# shredmaster.net
KiCad netlist of a schematic drawn in EAGLE
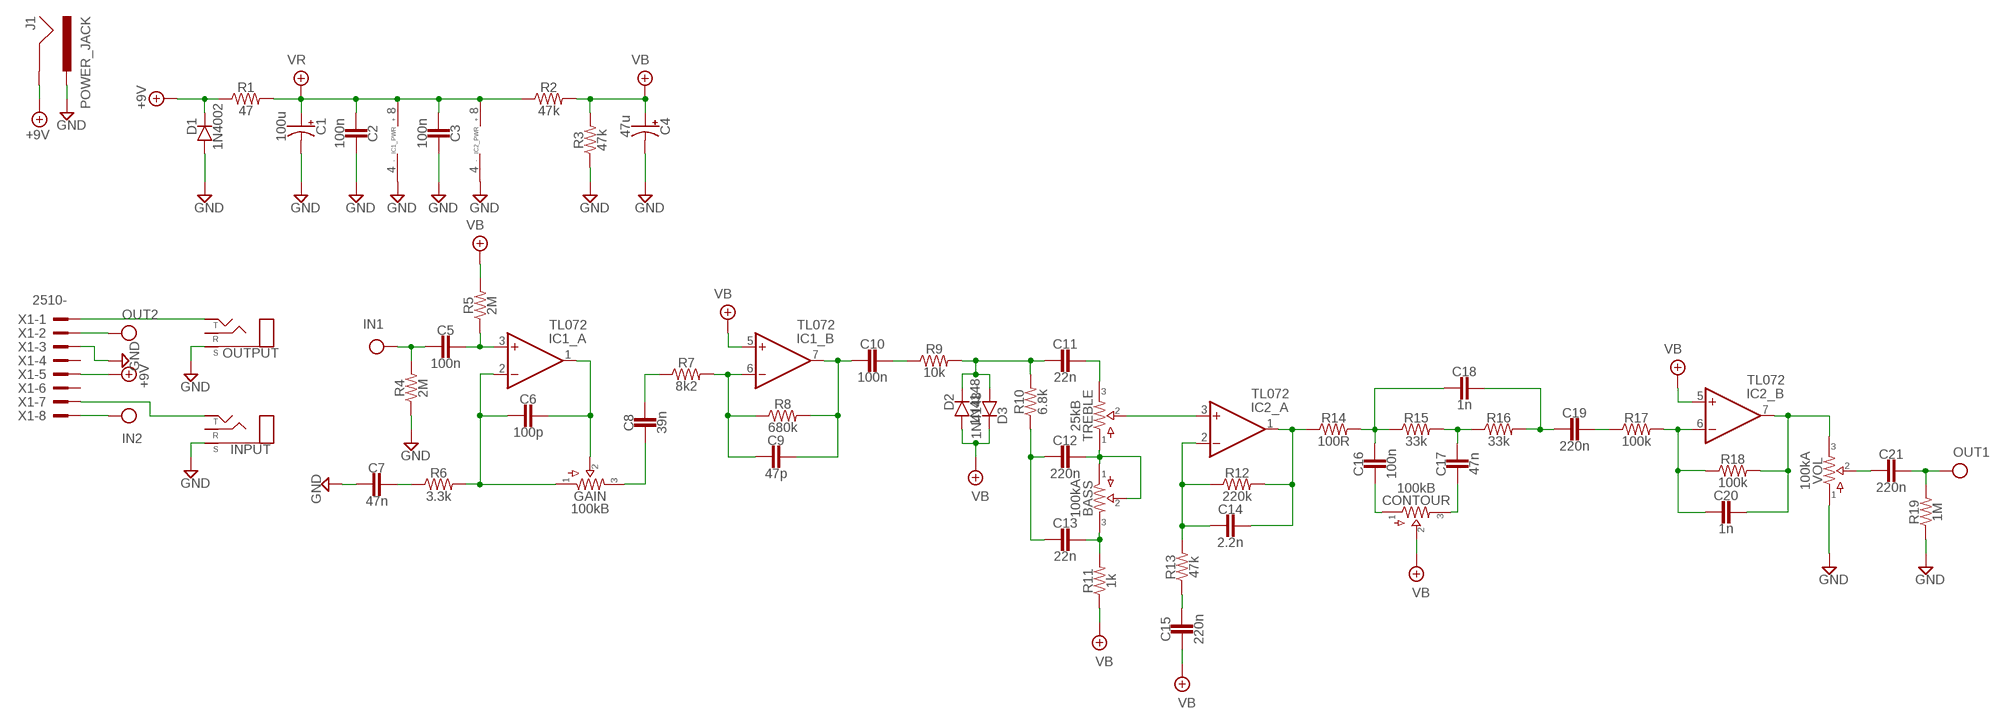
[diagram p0: schematic, sheet 1]

(export (version "E")
  (design (tool "Eeschema 10.0.6"))
  (components
    (comp (ref "BASS")
      (value "100kA")
      (footprint "eagle-import:16MM")
      (libsource (lib "eagle-import") (part "POTS16MM"))
    )
    (comp (ref "C1")
      (value "100u")
      (footprint "eagle-import:040_020")
      (libsource (lib "eagle-import") (part "0400"))
    )
    (comp (ref "C2")
      (value "100n")
      (footprint "eagle-import:050X030_025_2")
      (libsource (lib "eagle-import") (part "CER/FILM2"))
    )
    (comp (ref "C3")
      (value "100n")
      (footprint "eagle-import:050X030_025_2")
      (libsource (lib "eagle-import") (part "CER/FILM2"))
    )
    (comp (ref "C4")
      (value "47u")
      (footprint "eagle-import:040_020")
      (libsource (lib "eagle-import") (part "0400"))
    )
    (comp (ref "C5")
      (value "100n")
      (footprint "eagle-import:BOX_SMALL")
      (libsource (lib "eagle-import") (part "CER/FILMBOX.1"))
    )
    (comp (ref "C6")
      (value "100p")
      (footprint "eagle-import:050X030_025_2")
      (libsource (lib "eagle-import") (part "CER/FILM2"))
    )
    (comp (ref "C7")
      (value "47n")
      (footprint "eagle-import:BOX_SMALL")
      (libsource (lib "eagle-import") (part "CER/FILMBOX.1"))
    )
    (comp (ref "C8")
      (value "39n")
      (footprint "eagle-import:BOX_SMALL")
      (libsource (lib "eagle-import") (part "CER/FILMBOX.1"))
    )
    (comp (ref "C9")
      (value "47p")
      (footprint "eagle-import:050X030_025_2")
      (libsource (lib "eagle-import") (part "CER/FILM2"))
    )
    (comp (ref "C10")
      (value "100n")
      (footprint "eagle-import:BOX_SMALL")
      (libsource (lib "eagle-import") (part "CER/FILMBOX.1"))
    )
    (comp (ref "C11")
      (value "22n")
      (footprint "eagle-import:BOX_SMALL")
      (libsource (lib "eagle-import") (part "CER/FILMBOX.1"))
    )
    (comp (ref "C12")
      (value "220n")
      (footprint "eagle-import:BOX_SMALL")
      (libsource (lib "eagle-import") (part "CER/FILMBOX.1"))
    )
    (comp (ref "C13")
      (value "22n")
      (footprint "eagle-import:BOX_SMALL")
      (libsource (lib "eagle-import") (part "CER/FILMBOX.1"))
    )
    (comp (ref "C14")
      (value "2.2n")
      (footprint "eagle-import:BOX_SMALL")
      (libsource (lib "eagle-import") (part "CER/FILMBOX.1"))
    )
    (comp (ref "C15")
      (value "220n")
      (footprint "eagle-import:BOX_SMALL")
      (libsource (lib "eagle-import") (part "CER/FILMBOX.1"))
    )
    (comp (ref "C16")
      (value "100n")
      (footprint "eagle-import:BOX_SMALL")
      (libsource (lib "eagle-import") (part "CER/FILMBOX.1"))
    )
    (comp (ref "C17")
      (value "47n")
      (footprint "eagle-import:BOX_SMALL")
      (libsource (lib "eagle-import") (part "CER/FILMBOX.1"))
    )
    (comp (ref "C18")
      (value "1n")
      (footprint "eagle-import:BOX_SMALL")
      (libsource (lib "eagle-import") (part "CER/FILMBOX.1"))
    )
    (comp (ref "C19")
      (value "220n")
      (footprint "eagle-import:BOX_SMALL")
      (libsource (lib "eagle-import") (part "CER/FILMBOX.1"))
    )
    (comp (ref "C20")
      (value "1n")
      (footprint "eagle-import:BOX_SMALL")
      (libsource (lib "eagle-import") (part "CER/FILMBOX.1"))
    )
    (comp (ref "C21")
      (value "220n")
      (footprint "eagle-import:BOX_SMALL")
      (libsource (lib "eagle-import") (part "CER/FILMBOX.1"))
    )
    (comp (ref "CONTOUR")
      (value "100kB")
      (footprint "eagle-import:16MM")
      (libsource (lib "eagle-import") (part "POTS16MM"))
    )
    (comp (ref "D1")
      (value "1N4002")
      (footprint "eagle-import:DO41-2")
      (libsource (lib "eagle-import") (part "DO41.2"))
    )
    (comp (ref "D2")
      (value "1N4148")
      (footprint "eagle-import:DO35-2")
      (libsource (lib "eagle-import") (part "DO35.2"))
    )
    (comp (ref "D3")
      (value "1N4148")
      (footprint "eagle-import:DO35-2")
      (libsource (lib "eagle-import") (part "DO35.2"))
    )
    (comp (ref "GAIN")
      (value "100kB")
      (footprint "eagle-import:16MM")
      (libsource (lib "eagle-import") (part "POTS16MM"))
    )
    (comp (ref "IC1")
      (value "TL072")
      (footprint "eagle-import:DIL08")
      (libsource (lib "eagle-import") (part "DUALTH"))
    )
    (comp (ref "IC2")
      (value "TL072")
      (footprint "eagle-import:DIL08")
      (libsource (lib "eagle-import") (part "DUALTH"))
    )
    (comp (ref "INPUT")
      (value "STEREONMJ")
      (footprint "eagle-import:NMJ6HCD2")
      (libsource (lib "eagle-import") (part "STEREONMJ"))
    )
    (comp (ref "J1")
      (value "POWER_JACK")
      (footprint "eagle-import:POWER_JACK_PTH")
      (libsource (lib "eagle-import") (part "POWER_JACK"))
    )
    (comp (ref "OUTPUT")
      (value "STEREONMJ")
      (footprint "eagle-import:NMJ6HCD2")
      (libsource (lib "eagle-import") (part "STEREONMJ"))
    )
    (comp (ref "R1")
      (value "47")
      (footprint "eagle-import:R0207_3")
      (libsource (lib "eagle-import") (part "R_.3B"))
    )
    (comp (ref "R2")
      (value "47k")
      (footprint "eagle-import:R0207_3")
      (libsource (lib "eagle-import") (part "R_.3B"))
    )
    (comp (ref "R3")
      (value "47k")
      (footprint "eagle-import:R0207_3")
      (libsource (lib "eagle-import") (part "R_.3B"))
    )
    (comp (ref "R4")
      (value "2M")
      (footprint "eagle-import:R0207_3")
      (libsource (lib "eagle-import") (part "R_.3B"))
    )
    (comp (ref "R5")
      (value "2M")
      (footprint "eagle-import:R0207_3")
      (libsource (lib "eagle-import") (part "R_.3B"))
    )
    (comp (ref "R6")
      (value "3.3k")
      (footprint "eagle-import:R0207_3")
      (libsource (lib "eagle-import") (part "R_.3B"))
    )
    (comp (ref "R7")
      (value "8k2")
      (footprint "eagle-import:R0207_3")
      (libsource (lib "eagle-import") (part "R_.3B"))
    )
    (comp (ref "R8")
      (value "680k")
      (footprint "eagle-import:R0207_3")
      (libsource (lib "eagle-import") (part "R_.3B"))
    )
    (comp (ref "R9")
      (value "10k")
      (footprint "eagle-import:R0207_3")
      (libsource (lib "eagle-import") (part "R_.3B"))
    )
    (comp (ref "R10")
      (value "6.8k")
      (footprint "eagle-import:R0207_3")
      (libsource (lib "eagle-import") (part "R_.3B"))
    )
    (comp (ref "R11")
      (value "1k")
      (footprint "eagle-import:R0207_3")
      (libsource (lib "eagle-import") (part "R_.3B"))
    )
    (comp (ref "R12")
      (value "220k")
      (footprint "eagle-import:R0207_3")
      (libsource (lib "eagle-import") (part "R_.3B"))
    )
    (comp (ref "R13")
      (value "47k")
      (footprint "eagle-import:R0207_3")
      (libsource (lib "eagle-import") (part "R_.3B"))
    )
    (comp (ref "R14")
      (value "100R")
      (footprint "eagle-import:R0207_3")
      (libsource (lib "eagle-import") (part "R_.3B"))
    )
    (comp (ref "R15")
      (value "33k")
      (footprint "eagle-import:R0207_3")
      (libsource (lib "eagle-import") (part "R_.3B"))
    )
    (comp (ref "R16")
      (value "33k")
      (footprint "eagle-import:R0207_3")
      (libsource (lib "eagle-import") (part "R_.3B"))
    )
    (comp (ref "R17")
      (value "100k")
      (footprint "eagle-import:R0207_3")
      (libsource (lib "eagle-import") (part "R_.3B"))
    )
    (comp (ref "R18")
      (value "100k")
      (footprint "eagle-import:R0207_3")
      (libsource (lib "eagle-import") (part "R_.3B"))
    )
    (comp (ref "R19")
      (value "1M")
      (footprint "eagle-import:R0207_3")
      (libsource (lib "eagle-import") (part "R_.3B"))
    )
    (comp (ref "TREBLE")
      (value "25kB")
      (footprint "eagle-import:16MM")
      (libsource (lib "eagle-import") (part "POTS16MM"))
    )
    (comp (ref "VOL")
      (value "100kA")
      (footprint "eagle-import:16MM")
      (libsource (lib "eagle-import") (part "POTS16MM"))
    )
    (comp (ref "X1")
      (value "2510-")
      (footprint "eagle-import:PAK100_2500-10")
      (fields (field (name "MF") "3M") (field (name "MPN") "2510-6002UB"))
      (libsource (lib "eagle-import") (part "2510-"))
    )
  )
  (nets
    (net (code "1") (name "+9V") (class "Default")
      (node (ref "D1") (pin "C") (pinfunction "C_C") (pintype "passive"))
      (node (ref "J1") (pin "GND") (pinfunction "GND_GND") (pintype "bidirectional"))
      (node (ref "R1") (pin "1") (pinfunction "1_1") (pintype "passive"))
      (node (ref "X1") (pin "5") (pinfunction "KL_5") (pintype "passive"))
    )
    (net (code "2") (name "GND") (class "Default")
      (node (ref "C1") (pin "-") (pinfunction "-_-") (pintype "passive"))
      (node (ref "C2") (pin "1") (pinfunction "1_1") (pintype "passive"))
      (node (ref "C3") (pin "1") (pinfunction "1_1") (pintype "passive"))
      (node (ref "C4") (pin "-") (pinfunction "-_-") (pintype "passive"))
      (node (ref "C7") (pin "2") (pinfunction "2_2") (pintype "passive"))
      (node (ref "D1") (pin "A") (pinfunction "A_A") (pintype "passive"))
      (node (ref "IC1") (pin "4") (pinfunction "V-_4") (pintype "power_in"))
      (node (ref "IC2") (pin "4") (pinfunction "V-_4") (pintype "power_in"))
      (node (ref "INPUT") (pin "S") (pinfunction "S_S") (pintype "passive"))
      (node (ref "J1") (pin "PWR") (pinfunction "PWR_PWR") (pintype "bidirectional"))
      (node (ref "OUTPUT") (pin "S") (pinfunction "S_S") (pintype "passive"))
      (node (ref "R19") (pin "1") (pinfunction "1_1") (pintype "passive"))
      (node (ref "R3") (pin "1") (pinfunction "1_1") (pintype "passive"))
      (node (ref "R4") (pin "1") (pinfunction "1_1") (pintype "passive"))
      (node (ref "VOL") (pin "1") (pinfunction "1_1") (pintype "passive"))
      (node (ref "X1") (pin "3") (pinfunction "KL_3") (pintype "passive"))
    )
    (net (code "3") (name "IN") (class "Default")
      (node (ref "C5") (pin "2") (pinfunction "2_2") (pintype "passive"))
      (node (ref "R4") (pin "2") (pinfunction "2_2") (pintype "passive"))
      (node (ref "X1") (pin "8") (pinfunction "KL_8") (pintype "passive"))
    )
    (net (code "4") (name "Net-(BASS-Pad1)") (class "Default")
      (node (ref "BASS") (pin "1") (pinfunction "1_1") (pintype "passive"))
      (node (ref "BASS") (pin "2") (pinfunction "2_2") (pintype "passive"))
      (node (ref "C12") (pin "1") (pinfunction "1_1") (pintype "passive"))
      (node (ref "TREBLE") (pin "1") (pinfunction "1_1") (pintype "passive"))
    )
    (net (code "5") (name "Net-(BASS-Pad3)") (class "Default")
      (node (ref "BASS") (pin "3") (pinfunction "3_3") (pintype "passive"))
      (node (ref "C13") (pin "1") (pinfunction "1_1") (pintype "passive"))
      (node (ref "R11") (pin "2") (pinfunction "2_2") (pintype "passive"))
    )
    (net (code "6") (name "Net-(C7-Pad1)") (class "Default")
      (node (ref "C7") (pin "1") (pinfunction "1_1") (pintype "passive"))
      (node (ref "R6") (pin "1") (pinfunction "1_1") (pintype "passive"))
    )
    (net (code "7") (name "Net-(C8-Pad1)") (class "Default")
      (node (ref "C8") (pin "1") (pinfunction "1_1") (pintype "passive"))
      (node (ref "R7") (pin "1") (pinfunction "1_1") (pintype "passive"))
    )
    (net (code "8") (name "Net-(C8-Pad2)") (class "Default")
      (node (ref "C8") (pin "2") (pinfunction "2_2") (pintype "passive"))
      (node (ref "GAIN") (pin "3") (pinfunction "3_3") (pintype "passive"))
    )
    (net (code "9") (name "Net-(C10-Pad1)") (class "Default")
      (node (ref "C10") (pin "1") (pinfunction "1_1") (pintype "passive"))
      (node (ref "R9") (pin "1") (pinfunction "1_1") (pintype "passive"))
    )
    (net (code "10") (name "Net-(C11-Pad1)") (class "Default")
      (node (ref "C11") (pin "1") (pinfunction "1_1") (pintype "passive"))
      (node (ref "TREBLE") (pin "3") (pinfunction "3_3") (pintype "passive"))
    )
    (net (code "11") (name "Net-(C11-Pad2)") (class "Default")
      (node (ref "C11") (pin "2") (pinfunction "2_2") (pintype "passive"))
      (node (ref "D2") (pin "C") (pinfunction "C_C") (pintype "passive"))
      (node (ref "D3") (pin "A") (pinfunction "A_A") (pintype "passive"))
      (node (ref "R10") (pin "2") (pinfunction "2_2") (pintype "passive"))
      (node (ref "R9") (pin "2") (pinfunction "2_2") (pintype "passive"))
    )
    (net (code "12") (name "Net-(C12-Pad2)") (class "Default")
      (node (ref "C12") (pin "2") (pinfunction "2_2") (pintype "passive"))
      (node (ref "C13") (pin "2") (pinfunction "2_2") (pintype "passive"))
      (node (ref "R10") (pin "1") (pinfunction "1_1") (pintype "passive"))
    )
    (net (code "13") (name "Net-(C15-Pad1)") (class "Default")
      (node (ref "C15") (pin "1") (pinfunction "1_1") (pintype "passive"))
      (node (ref "R13") (pin "1") (pinfunction "1_1") (pintype "passive"))
    )
    (net (code "14") (name "Net-(C16-Pad1)") (class "Default")
      (node (ref "C16") (pin "1") (pinfunction "1_1") (pintype "passive"))
      (node (ref "C18") (pin "2") (pinfunction "2_2") (pintype "passive"))
      (node (ref "R14") (pin "2") (pinfunction "2_2") (pintype "passive"))
      (node (ref "R15") (pin "1") (pinfunction "1_1") (pintype "passive"))
    )
    (net (code "15") (name "Net-(C16-Pad2)") (class "Default")
      (node (ref "C16") (pin "2") (pinfunction "2_2") (pintype "passive"))
      (node (ref "CONTOUR") (pin "1") (pinfunction "1_1") (pintype "passive"))
    )
    (net (code "16") (name "Net-(C17-Pad1)") (class "Default")
      (node (ref "C17") (pin "1") (pinfunction "1_1") (pintype "passive"))
      (node (ref "R15") (pin "2") (pinfunction "2_2") (pintype "passive"))
      (node (ref "R16") (pin "1") (pinfunction "1_1") (pintype "passive"))
    )
    (net (code "17") (name "Net-(C17-Pad2)") (class "Default")
      (node (ref "C17") (pin "2") (pinfunction "2_2") (pintype "passive"))
      (node (ref "CONTOUR") (pin "3") (pinfunction "3_3") (pintype "passive"))
    )
    (net (code "18") (name "Net-(C18-Pad1)") (class "Default")
      (node (ref "C18") (pin "1") (pinfunction "1_1") (pintype "passive"))
      (node (ref "C19") (pin "2") (pinfunction "2_2") (pintype "passive"))
      (node (ref "R16") (pin "2") (pinfunction "2_2") (pintype "passive"))
    )
    (net (code "19") (name "Net-(C19-Pad1)") (class "Default")
      (node (ref "C19") (pin "1") (pinfunction "1_1") (pintype "passive"))
      (node (ref "R17") (pin "1") (pinfunction "1_1") (pintype "passive"))
    )
    (net (code "20") (name "Net-(C21-Pad2)") (class "Default")
      (node (ref "C21") (pin "2") (pinfunction "2_2") (pintype "passive"))
      (node (ref "VOL") (pin "2") (pinfunction "2_2") (pintype "passive"))
    )
    (net (code "21") (name "Net-(IC1A-+IN)") (class "Default")
      (node (ref "C5") (pin "1") (pinfunction "1_1") (pintype "passive"))
      (node (ref "IC1") (pin "3") (pinfunction "+IN_3") (pintype "input"))
      (node (ref "R5") (pin "1") (pinfunction "1_1") (pintype "passive"))
    )
    (net (code "22") (name "Net-(IC1A--IN)") (class "Default")
      (node (ref "C6") (pin "2") (pinfunction "2_2") (pintype "passive"))
      (node (ref "GAIN") (pin "1") (pinfunction "1_1") (pintype "passive"))
      (node (ref "IC1") (pin "2") (pinfunction "-IN_2") (pintype "input"))
      (node (ref "R6") (pin "2") (pinfunction "2_2") (pintype "passive"))
    )
    (net (code "23") (name "Net-(IC1A-OUT)") (class "Default")
      (node (ref "C6") (pin "1") (pinfunction "1_1") (pintype "passive"))
      (node (ref "GAIN") (pin "2") (pinfunction "2_2") (pintype "passive"))
      (node (ref "IC1") (pin "1") (pinfunction "OUT_1") (pintype "output"))
    )
    (net (code "24") (name "Net-(IC1B--IN)") (class "Default")
      (node (ref "C9") (pin "2") (pinfunction "2_2") (pintype "passive"))
      (node (ref "IC1") (pin "6") (pinfunction "-IN_6") (pintype "input"))
      (node (ref "R7") (pin "2") (pinfunction "2_2") (pintype "passive"))
      (node (ref "R8") (pin "1") (pinfunction "1_1") (pintype "passive"))
    )
    (net (code "25") (name "Net-(IC1B-OUT)") (class "Default")
      (node (ref "C10") (pin "2") (pinfunction "2_2") (pintype "passive"))
      (node (ref "C9") (pin "1") (pinfunction "1_1") (pintype "passive"))
      (node (ref "IC1") (pin "7") (pinfunction "OUT_7") (pintype "output"))
      (node (ref "R8") (pin "2") (pinfunction "2_2") (pintype "passive"))
    )
    (net (code "26") (name "Net-(IC2A-+IN)") (class "Default")
      (node (ref "IC2") (pin "3") (pinfunction "+IN_3") (pintype "input"))
      (node (ref "TREBLE") (pin "2") (pinfunction "2_2") (pintype "passive"))
    )
    (net (code "27") (name "Net-(IC2A--IN)") (class "Default")
      (node (ref "C14") (pin "2") (pinfunction "2_2") (pintype "passive"))
      (node (ref "IC2") (pin "2") (pinfunction "-IN_2") (pintype "input"))
      (node (ref "R12") (pin "1") (pinfunction "1_1") (pintype "passive"))
      (node (ref "R13") (pin "2") (pinfunction "2_2") (pintype "passive"))
    )
    (net (code "28") (name "Net-(IC2A-OUT)") (class "Default")
      (node (ref "C14") (pin "1") (pinfunction "1_1") (pintype "passive"))
      (node (ref "IC2") (pin "1") (pinfunction "OUT_1") (pintype "output"))
      (node (ref "R12") (pin "2") (pinfunction "2_2") (pintype "passive"))
      (node (ref "R14") (pin "1") (pinfunction "1_1") (pintype "passive"))
    )
    (net (code "29") (name "Net-(IC2B--IN)") (class "Default")
      (node (ref "C20") (pin "2") (pinfunction "2_2") (pintype "passive"))
      (node (ref "IC2") (pin "6") (pinfunction "-IN_6") (pintype "input"))
      (node (ref "R17") (pin "2") (pinfunction "2_2") (pintype "passive"))
      (node (ref "R18") (pin "1") (pinfunction "1_1") (pintype "passive"))
    )
    (net (code "30") (name "Net-(IC2B-OUT)") (class "Default")
      (node (ref "C20") (pin "1") (pinfunction "1_1") (pintype "passive"))
      (node (ref "IC2") (pin "7") (pinfunction "OUT_7") (pintype "output"))
      (node (ref "R18") (pin "2") (pinfunction "2_2") (pintype "passive"))
      (node (ref "VOL") (pin "3") (pinfunction "3_3") (pintype "passive"))
    )
    (net (code "31") (name "Net-(X1A-KL)") (class "Default")
      (node (ref "OUTPUT") (pin "T") (pinfunction "T_T") (pintype "passive"))
      (node (ref "X1") (pin "1") (pinfunction "KL_1") (pintype "passive"))
    )
    (net (code "32") (name "Net-(X1G-KL)") (class "Default")
      (node (ref "INPUT") (pin "T") (pinfunction "T_T") (pintype "passive"))
      (node (ref "X1") (pin "7") (pinfunction "KL_7") (pintype "passive"))
    )
    (net (code "33") (name "OUT") (class "Default")
      (node (ref "C21") (pin "1") (pinfunction "1_1") (pintype "passive"))
      (node (ref "R19") (pin "2") (pinfunction "2_2") (pintype "passive"))
      (node (ref "X1") (pin "2") (pinfunction "KL_2") (pintype "passive"))
    )
    (net (code "34") (name "VB") (class "Default")
      (node (ref "C15") (pin "2") (pinfunction "2_2") (pintype "passive"))
      (node (ref "C4") (pin "+") (pinfunction "+_+") (pintype "passive"))
      (node (ref "CONTOUR") (pin "2") (pinfunction "2_2") (pintype "passive"))
      (node (ref "D2") (pin "A") (pinfunction "A_A") (pintype "passive"))
      (node (ref "D3") (pin "C") (pinfunction "C_C") (pintype "passive"))
      (node (ref "IC1") (pin "5") (pinfunction "+IN_5") (pintype "input"))
      (node (ref "IC2") (pin "5") (pinfunction "+IN_5") (pintype "input"))
      (node (ref "R11") (pin "1") (pinfunction "1_1") (pintype "passive"))
      (node (ref "R2") (pin "2") (pinfunction "2_2") (pintype "passive"))
      (node (ref "R3") (pin "2") (pinfunction "2_2") (pintype "passive"))
      (node (ref "R5") (pin "2") (pinfunction "2_2") (pintype "passive"))
    )
    (net (code "35") (name "VR") (class "Default")
      (node (ref "C1") (pin "+") (pinfunction "+_+") (pintype "passive"))
      (node (ref "C2") (pin "2") (pinfunction "2_2") (pintype "passive"))
      (node (ref "C3") (pin "2") (pinfunction "2_2") (pintype "passive"))
      (node (ref "IC1") (pin "8") (pinfunction "V+_8") (pintype "power_in"))
      (node (ref "IC2") (pin "8") (pinfunction "V+_8") (pintype "power_in"))
      (node (ref "R1") (pin "2") (pinfunction "2_2") (pintype "passive"))
      (node (ref "R2") (pin "1") (pinfunction "1_1") (pintype "passive"))
    )
    (net (code "36") (name "unconnected-(INPUT-PadR)") (class "Default")
      (node (ref "INPUT") (pin "R") (pinfunction "R_R") (pintype "passive"))
    )
    (net (code "37") (name "unconnected-(OUTPUT-PadR)") (class "Default")
      (node (ref "OUTPUT") (pin "R") (pinfunction "R_R") (pintype "passive"))
    )
    (net (code "38") (name "unconnected-(X1D-KL-Pad4)") (class "Default")
      (node (ref "X1") (pin "4") (pinfunction "KL_4") (pintype "passive"))
    )
    (net (code "39") (name "unconnected-(X1F-KL-Pad6)") (class "Default")
      (node (ref "X1") (pin "6") (pinfunction "KL_6") (pintype "passive"))
    )
  )
)
